# Qwiic_TCA9534.net
KiCad netlist of a schematic drawn in EAGLE
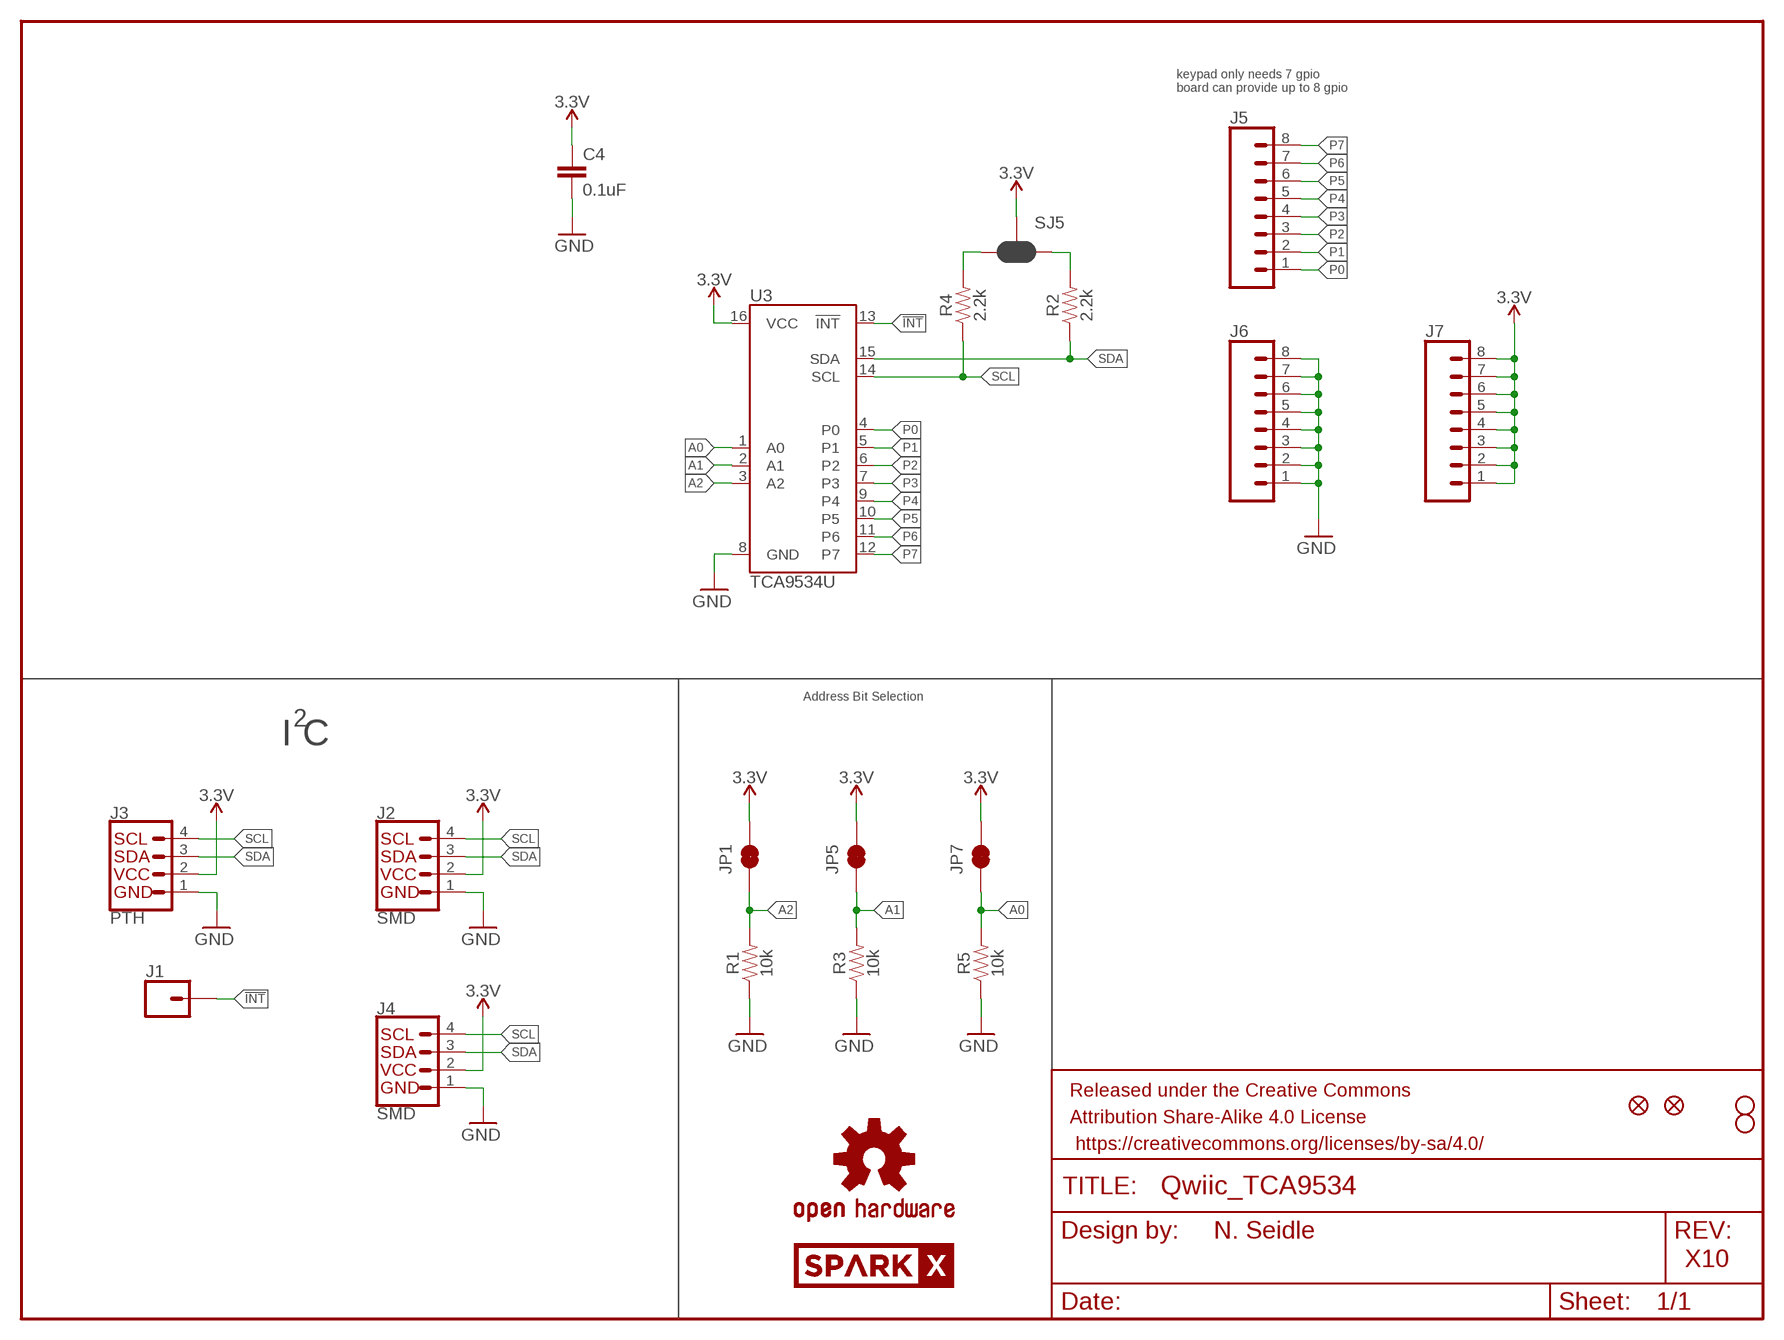
[diagram p0: schematic, sheet 1]

(export (version "E")
  (design (tool "Eeschema 10.0.6"))
  (components
    (comp (ref "C4")
      (value "0.1uF")
      (footprint "eagle-import:0603")
      (libsource (lib "eagle-import") (part "0.1UF-0603-25V-(+80/-20%)"))
    )
    (comp (ref "FRAME1")
      (value "FRAME-LETTER")
      (footprint "eagle-import:CREATIVE_COMMONS")
      (libsource (lib "eagle-import") (part "FRAME-LETTER"))
    )
    (comp (ref "J1")
      (value "CONN_01PTH_NO_SILK_YES_STOP")
      (footprint "eagle-import:1X01_NO_SILK")
      (libsource (lib "eagle-import") (part "CONN_01PTH_NO_SILK_YES_STOP"))
    )
    (comp (ref "J2")
      (value "SMD")
      (footprint "eagle-import:1X04_1MM_RA")
      (libsource (lib "eagle-import") (part "I2C_STANDARDJS-1MM"))
    )
    (comp (ref "J3")
      (value "PTH")
      (footprint "eagle-import:1X04_NO_SILK")
      (libsource (lib "eagle-import") (part "I2C_STANDARD_NO_SILK"))
    )
    (comp (ref "J4")
      (value "SMD")
      (footprint "eagle-import:1X04_1MM_RA")
      (libsource (lib "eagle-import") (part "I2C_STANDARDJS-1MM"))
    )
    (comp (ref "J5")
      (value "CONN_08NO_SILK_FEMALE_PTH")
      (footprint "eagle-import:1X08_NO_SILK")
      (libsource (lib "eagle-import") (part "CONN_08NO_SILK_FEMALE_PTH"))
    )
    (comp (ref "J6")
      (value "CONN_08NO_SILK_FEMALE_PTH")
      (footprint "eagle-import:1X08_NO_SILK")
      (libsource (lib "eagle-import") (part "CONN_08NO_SILK_FEMALE_PTH"))
    )
    (comp (ref "J7")
      (value "CONN_08NO_SILK_FEMALE_PTH")
      (footprint "eagle-import:1X08_NO_SILK")
      (libsource (lib "eagle-import") (part "CONN_08NO_SILK_FEMALE_PTH"))
    )
    (comp (ref "JP1")
      (value "JUMPER-SMT_2_NC_TRACE_NO-SILK")
      (footprint "eagle-import:SMT-JUMPER_2_NC_TRACE_NO-SILK")
      (libsource (lib "eagle-import") (part "JUMPER-SMT_2_NC_TRACE_NO-SILK"))
    )
    (comp (ref "JP2")
      (value "FIDUCIALUFIDUCIAL")
      (footprint "eagle-import:MICRO-FIDUCIAL")
      (libsource (lib "eagle-import") (part "FIDUCIALUFIDUCIAL"))
    )
    (comp (ref "JP3")
      (value "STAND-OFF")
      (footprint "eagle-import:STAND-OFF")
      (libsource (lib "eagle-import") (part "STAND-OFF"))
    )
    (comp (ref "JP4")
      (value "STAND-OFF")
      (footprint "eagle-import:STAND-OFF")
      (libsource (lib "eagle-import") (part "STAND-OFF"))
    )
    (comp (ref "JP5")
      (value "JUMPER-SMT_2_NC_TRACE_NO-SILK")
      (footprint "eagle-import:SMT-JUMPER_2_NC_TRACE_NO-SILK")
      (libsource (lib "eagle-import") (part "JUMPER-SMT_2_NC_TRACE_NO-SILK"))
    )
    (comp (ref "JP6")
      (value "FIDUCIALUFIDUCIAL")
      (footprint "eagle-import:MICRO-FIDUCIAL")
      (libsource (lib "eagle-import") (part "FIDUCIALUFIDUCIAL"))
    )
    (comp (ref "JP7")
      (value "JUMPER-SMT_2_NC_TRACE_NO-SILK")
      (footprint "eagle-import:SMT-JUMPER_2_NC_TRACE_NO-SILK")
      (libsource (lib "eagle-import") (part "JUMPER-SMT_2_NC_TRACE_NO-SILK"))
    )
    (comp (ref "LOGO1")
      (value "OSHW-LOGOMINI")
      (footprint "eagle-import:OSHW-LOGO-MINI")
      (libsource (lib "eagle-import") (part "OSHW-LOGOMINI"))
    )
    (comp (ref "R1")
      (value "10k")
      (footprint "eagle-import:0603")
      (libsource (lib "eagle-import") (part "2.2KOHM-0603-1/10W-1%"))
    )
    (comp (ref "R2")
      (value "2.2k")
      (footprint "eagle-import:0603")
      (libsource (lib "eagle-import") (part "2.2KOHM-0603-1/10W-1%"))
    )
    (comp (ref "R3")
      (value "10k")
      (footprint "eagle-import:0603")
      (libsource (lib "eagle-import") (part "2.2KOHM-0603-1/10W-1%"))
    )
    (comp (ref "R4")
      (value "2.2k")
      (footprint "eagle-import:0603")
      (libsource (lib "eagle-import") (part "2.2KOHM-0603-1/10W-1%"))
    )
    (comp (ref "R5")
      (value "10k")
      (footprint "eagle-import:0603")
      (libsource (lib "eagle-import") (part "2.2KOHM-0603-1/10W-1%"))
    )
    (comp (ref "SJ5")
      (value "SMT-JUMPER-_3-2-NC-PASTE_TALL")
      (footprint "eagle-import:SMT-JUMPER_3-2-NC-PASTE_SILK_TALLER_A")
      (libsource (lib "eagle-import") (part "SMT-JUMPER-_3-2-NC-PASTE_TALL"))
    )
    (comp (ref "U$1")
      (value "SPARKX-LOGO3")
      (footprint "eagle-import:SPARKX-SMALL")
      (libsource (lib "eagle-import") (part "SPARKX-LOGO3"))
    )
    (comp (ref "U$2")
      (value "SPARKX-LOGO3")
      (footprint "eagle-import:SPARKX-SMALL")
      (libsource (lib "eagle-import") (part "SPARKX-LOGO3"))
    )
    (comp (ref "U3")
      (value "TCA9534U")
      (footprint "eagle-import:16SOIC")
      (libsource (lib "eagle-import") (part "TCA9534U"))
    )
  )
  (nets
    (net (code "1") (name "/~{INT}") (class "Default")
      (node (ref "J1") (pin "1") (pinfunction "1_1") (pintype "passive"))
      (node (ref "U3") (pin "13") (pinfunction "~{INT}_13") (pintype "bidirectional"))
    )
    (net (code "2") (name "3.3V") (class "Default")
      (node (ref "C4") (pin "1") (pinfunction "1_1") (pintype "passive"))
      (node (ref "J2") (pin "2") (pinfunction "VCC_2") (pintype "power_in"))
      (node (ref "J3") (pin "2") (pinfunction "VCC_2") (pintype "power_in"))
      (node (ref "J4") (pin "2") (pinfunction "VCC_2") (pintype "power_in"))
      (node (ref "J7") (pin "1") (pinfunction "1_1") (pintype "passive"))
      (node (ref "J7") (pin "2") (pinfunction "2_2") (pintype "passive"))
      (node (ref "J7") (pin "3") (pinfunction "3_3") (pintype "passive"))
      (node (ref "J7") (pin "4") (pinfunction "4_4") (pintype "passive"))
      (node (ref "J7") (pin "5") (pinfunction "5_5") (pintype "passive"))
      (node (ref "J7") (pin "6") (pinfunction "6_6") (pintype "passive"))
      (node (ref "J7") (pin "7") (pinfunction "7_7") (pintype "passive"))
      (node (ref "J7") (pin "8") (pinfunction "8_8") (pintype "passive"))
      (node (ref "JP1") (pin "2") (pinfunction "2_2") (pintype "passive"))
      (node (ref "JP5") (pin "2") (pinfunction "2_2") (pintype "passive"))
      (node (ref "JP7") (pin "2") (pinfunction "2_2") (pintype "passive"))
      (node (ref "SJ5") (pin "2") (pinfunction "2_2") (pintype "passive"))
      (node (ref "U3") (pin "16") (pinfunction "VCC_16") (pintype "bidirectional"))
    )
    (net (code "3") (name "A0") (class "Default")
      (node (ref "JP7") (pin "1") (pinfunction "1_1") (pintype "passive"))
      (node (ref "R5") (pin "2") (pinfunction "2_2") (pintype "passive"))
      (node (ref "U3") (pin "1") (pinfunction "A0_1") (pintype "bidirectional"))
    )
    (net (code "4") (name "A1") (class "Default")
      (node (ref "JP5") (pin "1") (pinfunction "1_1") (pintype "passive"))
      (node (ref "R3") (pin "2") (pinfunction "2_2") (pintype "passive"))
      (node (ref "U3") (pin "2") (pinfunction "A1_2") (pintype "bidirectional"))
    )
    (net (code "5") (name "A2") (class "Default")
      (node (ref "JP1") (pin "1") (pinfunction "1_1") (pintype "passive"))
      (node (ref "R1") (pin "2") (pinfunction "2_2") (pintype "passive"))
      (node (ref "U3") (pin "3") (pinfunction "A2_3") (pintype "bidirectional"))
    )
    (net (code "6") (name "GND") (class "Default")
      (node (ref "C4") (pin "2") (pinfunction "2_2") (pintype "passive"))
      (node (ref "J2") (pin "1") (pinfunction "GND_1") (pintype "power_in"))
      (node (ref "J3") (pin "1") (pinfunction "GND_1") (pintype "power_in"))
      (node (ref "J4") (pin "1") (pinfunction "GND_1") (pintype "power_in"))
      (node (ref "J6") (pin "1") (pinfunction "1_1") (pintype "passive"))
      (node (ref "J6") (pin "2") (pinfunction "2_2") (pintype "passive"))
      (node (ref "J6") (pin "3") (pinfunction "3_3") (pintype "passive"))
      (node (ref "J6") (pin "4") (pinfunction "4_4") (pintype "passive"))
      (node (ref "J6") (pin "5") (pinfunction "5_5") (pintype "passive"))
      (node (ref "J6") (pin "6") (pinfunction "6_6") (pintype "passive"))
      (node (ref "J6") (pin "7") (pinfunction "7_7") (pintype "passive"))
      (node (ref "J6") (pin "8") (pinfunction "8_8") (pintype "passive"))
      (node (ref "R1") (pin "1") (pinfunction "1_1") (pintype "passive"))
      (node (ref "R3") (pin "1") (pinfunction "1_1") (pintype "passive"))
      (node (ref "R5") (pin "1") (pinfunction "1_1") (pintype "passive"))
      (node (ref "U3") (pin "8") (pinfunction "GND_8") (pintype "bidirectional"))
    )
    (net (code "7") (name "Net-(R2-Pad2)") (class "Default")
      (node (ref "R2") (pin "2") (pinfunction "2_2") (pintype "passive"))
      (node (ref "SJ5") (pin "1") (pinfunction "1_1") (pintype "passive"))
    )
    (net (code "8") (name "Net-(R4-Pad2)") (class "Default")
      (node (ref "R4") (pin "2") (pinfunction "2_2") (pintype "passive"))
      (node (ref "SJ5") (pin "3") (pinfunction "3_3") (pintype "passive"))
    )
    (net (code "9") (name "P0") (class "Default")
      (node (ref "J5") (pin "1") (pinfunction "1_1") (pintype "passive"))
      (node (ref "U3") (pin "4") (pinfunction "P0_4") (pintype "bidirectional"))
    )
    (net (code "10") (name "P1") (class "Default")
      (node (ref "J5") (pin "2") (pinfunction "2_2") (pintype "passive"))
      (node (ref "U3") (pin "5") (pinfunction "P1_5") (pintype "bidirectional"))
    )
    (net (code "11") (name "P2") (class "Default")
      (node (ref "J5") (pin "3") (pinfunction "3_3") (pintype "passive"))
      (node (ref "U3") (pin "6") (pinfunction "P2_6") (pintype "bidirectional"))
    )
    (net (code "12") (name "P3") (class "Default")
      (node (ref "J5") (pin "4") (pinfunction "4_4") (pintype "passive"))
      (node (ref "U3") (pin "7") (pinfunction "P3_7") (pintype "bidirectional"))
    )
    (net (code "13") (name "P4") (class "Default")
      (node (ref "J5") (pin "5") (pinfunction "5_5") (pintype "passive"))
      (node (ref "U3") (pin "9") (pinfunction "P4_9") (pintype "bidirectional"))
    )
    (net (code "14") (name "P5") (class "Default")
      (node (ref "J5") (pin "6") (pinfunction "6_6") (pintype "passive"))
      (node (ref "U3") (pin "10") (pinfunction "P5_10") (pintype "bidirectional"))
    )
    (net (code "15") (name "P6") (class "Default")
      (node (ref "J5") (pin "7") (pinfunction "7_7") (pintype "passive"))
      (node (ref "U3") (pin "11") (pinfunction "P6_11") (pintype "bidirectional"))
    )
    (net (code "16") (name "P7") (class "Default")
      (node (ref "J5") (pin "8") (pinfunction "8_8") (pintype "passive"))
      (node (ref "U3") (pin "12") (pinfunction "P7_12") (pintype "bidirectional"))
    )
    (net (code "17") (name "SCL") (class "Default")
      (node (ref "J2") (pin "4") (pinfunction "SCL_4") (pintype "passive"))
      (node (ref "J3") (pin "4") (pinfunction "SCL_4") (pintype "passive"))
      (node (ref "J4") (pin "4") (pinfunction "SCL_4") (pintype "passive"))
      (node (ref "R4") (pin "1") (pinfunction "1_1") (pintype "passive"))
      (node (ref "U3") (pin "14") (pinfunction "SCL_14") (pintype "bidirectional"))
    )
    (net (code "18") (name "SDA") (class "Default")
      (node (ref "J2") (pin "3") (pinfunction "SDA_3") (pintype "passive"))
      (node (ref "J3") (pin "3") (pinfunction "SDA_3") (pintype "passive"))
      (node (ref "J4") (pin "3") (pinfunction "SDA_3") (pintype "passive"))
      (node (ref "R2") (pin "1") (pinfunction "1_1") (pintype "passive"))
      (node (ref "U3") (pin "15") (pinfunction "SDA_15") (pintype "bidirectional"))
    )
  )
)
